# prototype.net
KiCad netlist of a schematic drawn in EAGLE
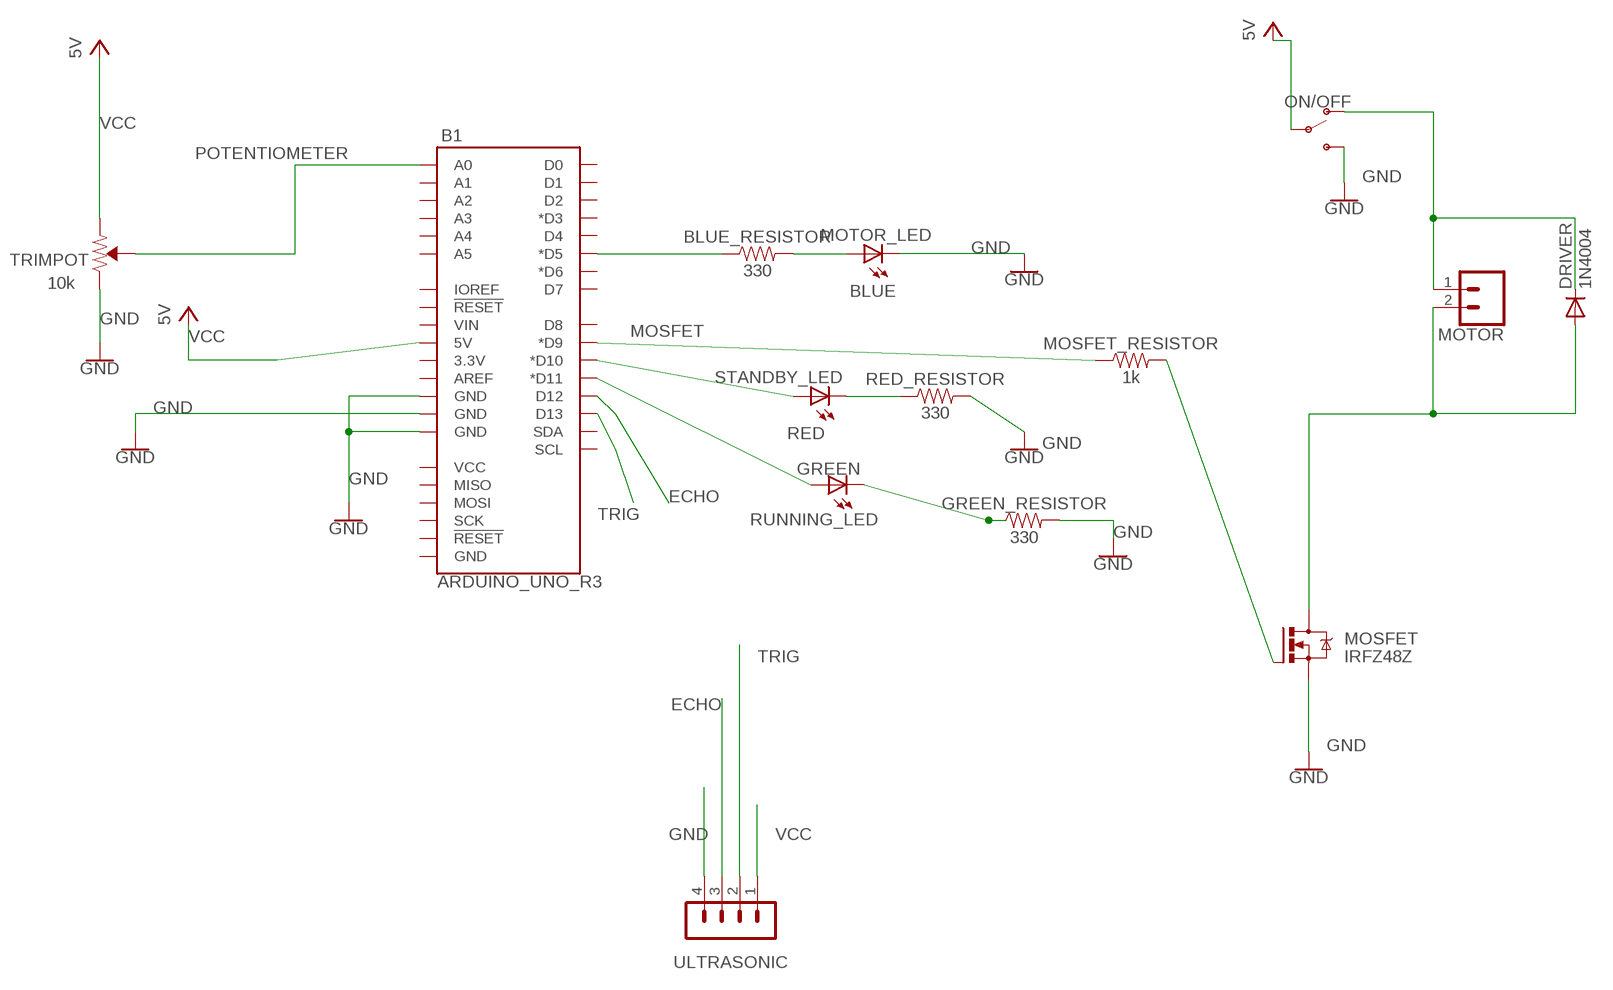
[diagram p0: schematic, sheet 1]

(export (version "E")
  (design (tool "Eeschema 10.0.6"))
  (components
    (comp (ref "B1")
      (value "ARDUINO_UNO_R3")
      (footprint "eagle-import:ARDUINO_R3")
      (libsource (lib "eagle-import") (part "ARDUINO_UNO_R3"))
    )
    (comp (ref "BLUE_RESISTOR")
      (value "330")
      (footprint "eagle-import:AXIAL-0.3")
      (libsource (lib "eagle-import") (part "1KOHM-HORIZ-1/4W-1%"))
    )
    (comp (ref "DRIVER")
      (value "1N4004")
      (footprint "eagle-import:DO41-10")
      (libsource (lib "eagle-import") (part "1N4004"))
    )
    (comp (ref "GREEN_RESISTOR")
      (value "330")
      (footprint "eagle-import:AXIAL-0.3")
      (libsource (lib "eagle-import") (part "330OHM-HORIZ-1/10W-5%"))
    )
    (comp (ref "MOSFET")
      (value "IRFZ48Z")
      (footprint "eagle-import:TO220BH")
      (libsource (lib "eagle-import") (part "IRFZ48Z"))
    )
    (comp (ref "MOSFET_RESISTOR")
      (value "1k")
      (footprint "eagle-import:AXIAL-0.3")
      (libsource (lib "eagle-import") (part "1KOHM-HORIZ-1/4W-1%"))
    )
    (comp (ref "MOTOR")
      (value "CONN_02")
      (footprint "eagle-import:1X02")
      (libsource (lib "eagle-import") (part "CONN_02"))
    )
    (comp (ref "MOTOR_LED")
      (value "BLUE")
      (footprint "eagle-import:LED5MM")
      (libsource (lib "eagle-import") (part "LED5MM"))
    )
    (comp (ref "ON/OFF")
      (value "SWITCH-SPDT-PTH-11.6X4.0MM")
      (footprint "eagle-import:SWITCH_SPDT_PTH_11.6X4.0MM")
      (libsource (lib "eagle-import") (part "SWITCH-SPDT-PTH-11.6X4.0MM"))
    )
    (comp (ref "RED_RESISTOR")
      (value "330")
      (footprint "eagle-import:AXIAL-0.3")
      (libsource (lib "eagle-import") (part "330OHM-HORIZ-1/10W-5%"))
    )
    (comp (ref "RUNNING_LED")
      (value "GREEN")
      (footprint "eagle-import:LED5MM")
      (libsource (lib "eagle-import") (part "LED5MM"))
    )
    (comp (ref "STANDBY_LED")
      (value "RED")
      (footprint "eagle-import:LED5MM")
      (libsource (lib "eagle-import") (part "LED5MM"))
    )
    (comp (ref "TRIMPOT")
      (value "10k")
      (footprint "eagle-import:TRIMPOT-PTH-3386U")
      (libsource (lib "eagle-import") (part "TRIMPOT-PTH-10MM-KNOB-1/2W-10%"))
    )
    (comp (ref "ULTRASONIC")
      (value "MA04-1")
      (footprint "eagle-import:MA04-1")
      (libsource (lib "eagle-import") (part "MA04-1"))
    )
  )
  (nets
    (net (code "1") (name "/ECHO") (class "Default")
      (node (ref "B1") (pin "D12") (pinfunction "D12_D12") (pintype "bidirectional"))
      (node (ref "ULTRASONIC") (pin "3") (pinfunction "3_3") (pintype "passive"))
    )
    (net (code "2") (name "/MOSFET") (class "Default")
      (node (ref "B1") (pin "D9") (pinfunction "*D9_D9") (pintype "bidirectional"))
      (node (ref "MOSFET_RESISTOR") (pin "P$1") (pinfunction "1_P$1") (pintype "passive"))
    )
    (net (code "3") (name "/POTENTIOMETER") (class "Default")
      (node (ref "B1") (pin "A0") (pinfunction "A0_A0") (pintype "bidirectional"))
      (node (ref "TRIMPOT") (pin "2") (pinfunction "WIPER_2") (pintype "passive"))
    )
    (net (code "4") (name "/TRIG") (class "Default")
      (node (ref "B1") (pin "D13") (pinfunction "D13_D13") (pintype "bidirectional"))
      (node (ref "ULTRASONIC") (pin "2") (pinfunction "2_2") (pintype "passive"))
    )
    (net (code "5") (name "5V") (class "Default")
      (node (ref "B1") (pin "5V") (pinfunction "5V_5V") (pintype "bidirectional"))
      (node (ref "ON/OFF") (pin "2") (pinfunction "P_2") (pintype "passive"))
      (node (ref "TRIMPOT") (pin "1") (pinfunction "CCW_1") (pintype "passive"))
      (node (ref "ULTRASONIC") (pin "1") (pinfunction "1_1") (pintype "passive"))
    )
    (net (code "6") (name "GND") (class "Default")
      (node (ref "B1") (pin "GND@2") (pinfunction "GND_GND@2") (pintype "bidirectional"))
      (node (ref "B1") (pin "GND@3") (pinfunction "GND_GND@3") (pintype "bidirectional"))
      (node (ref "B1") (pin "GND@4") (pinfunction "GND_GND@4") (pintype "bidirectional"))
      (node (ref "GREEN_RESISTOR") (pin "P$2") (pinfunction "2_P$2") (pintype "passive"))
      (node (ref "MOSFET") (pin "S") (pinfunction "S_S") (pintype "passive"))
      (node (ref "MOTOR_LED") (pin "K") (pinfunction "C_K") (pintype "passive"))
      (node (ref "ON/OFF") (pin "3") (pinfunction "S_3") (pintype "passive"))
      (node (ref "RED_RESISTOR") (pin "P$2") (pinfunction "2_P$2") (pintype "passive"))
      (node (ref "TRIMPOT") (pin "3") (pinfunction "CW_3") (pintype "passive"))
      (node (ref "ULTRASONIC") (pin "4") (pinfunction "4_4") (pintype "passive"))
    )
    (net (code "7") (name "Net-(B1-*D5)") (class "Default")
      (node (ref "B1") (pin "D5") (pinfunction "*D5_D5") (pintype "bidirectional"))
      (node (ref "BLUE_RESISTOR") (pin "P$1") (pinfunction "1_P$1") (pintype "passive"))
    )
    (net (code "8") (name "Net-(B1-*D10)") (class "Default")
      (node (ref "B1") (pin "D10") (pinfunction "*D10_D10") (pintype "bidirectional"))
      (node (ref "STANDBY_LED") (pin "A") (pinfunction "A_A") (pintype "passive"))
    )
    (net (code "9") (name "Net-(B1-*D11)") (class "Default")
      (node (ref "B1") (pin "D11") (pinfunction "*D11_D11") (pintype "bidirectional"))
      (node (ref "RUNNING_LED") (pin "A") (pinfunction "A_A") (pintype "passive"))
    )
    (net (code "10") (name "Net-(BLUE_RESISTOR-2)") (class "Default")
      (node (ref "BLUE_RESISTOR") (pin "P$2") (pinfunction "2_P$2") (pintype "passive"))
      (node (ref "MOTOR_LED") (pin "A") (pinfunction "A_A") (pintype "passive"))
    )
    (net (code "11") (name "Net-(DRIVER-PadA)") (class "Default")
      (node (ref "DRIVER") (pin "A") (pinfunction "A_A") (pintype "passive"))
      (node (ref "MOSFET") (pin "D") (pinfunction "D_D") (pintype "passive"))
      (node (ref "MOTOR") (pin "2") (pinfunction "2_2") (pintype "passive"))
    )
    (net (code "12") (name "Net-(GREEN_RESISTOR-1)") (class "Default")
      (node (ref "GREEN_RESISTOR") (pin "P$1") (pinfunction "1_P$1") (pintype "passive"))
      (node (ref "RUNNING_LED") (pin "K") (pinfunction "C_K") (pintype "passive"))
    )
    (net (code "13") (name "Net-(MOSFET_RESISTOR-2)") (class "Default")
      (node (ref "MOSFET") (pin "G") (pinfunction "G_G") (pintype "passive"))
      (node (ref "MOSFET_RESISTOR") (pin "P$2") (pinfunction "2_P$2") (pintype "passive"))
    )
    (net (code "14") (name "Net-(ON/OFF-O)") (class "Default")
      (node (ref "DRIVER") (pin "C") (pinfunction "C_C") (pintype "passive"))
      (node (ref "MOTOR") (pin "1") (pinfunction "1_1") (pintype "passive"))
      (node (ref "ON/OFF") (pin "1") (pinfunction "O_1") (pintype "passive"))
    )
    (net (code "15") (name "Net-(RED_RESISTOR-1)") (class "Default")
      (node (ref "RED_RESISTOR") (pin "P$1") (pinfunction "1_P$1") (pintype "passive"))
      (node (ref "STANDBY_LED") (pin "K") (pinfunction "C_K") (pintype "passive"))
    )
    (net (code "16") (name "unconnected-(B1-*D3-PadD3)") (class "Default")
      (node (ref "B1") (pin "D3") (pinfunction "*D3_D3") (pintype "bidirectional"))
    )
    (net (code "17") (name "unconnected-(B1-*D6-PadD6)") (class "Default")
      (node (ref "B1") (pin "D6") (pinfunction "*D6_D6") (pintype "bidirectional"))
    )
    (net (code "18") (name "unconnected-(B1-GND-PadGND@1)") (class "Default")
      (node (ref "B1") (pin "GND@1") (pinfunction "GND_GND@1") (pintype "bidirectional"))
    )
    (net (code "19") (name "unconnected-(B1-Pad3.3V)") (class "Default")
      (node (ref "B1") (pin "3.3V") (pinfunction "3.3V_3.3V") (pintype "bidirectional"))
    )
    (net (code "20") (name "unconnected-(B1-PadA1)") (class "Default")
      (node (ref "B1") (pin "A1") (pinfunction "A1_A1") (pintype "bidirectional"))
    )
    (net (code "21") (name "unconnected-(B1-PadA2)") (class "Default")
      (node (ref "B1") (pin "A2") (pinfunction "A2_A2") (pintype "bidirectional"))
    )
    (net (code "22") (name "unconnected-(B1-PadA3)") (class "Default")
      (node (ref "B1") (pin "A3") (pinfunction "A3_A3") (pintype "bidirectional"))
    )
    (net (code "23") (name "unconnected-(B1-PadA4)") (class "Default")
      (node (ref "B1") (pin "A4") (pinfunction "A4_A4") (pintype "bidirectional"))
    )
    (net (code "24") (name "unconnected-(B1-PadA5)") (class "Default")
      (node (ref "B1") (pin "A5") (pinfunction "A5_A5") (pintype "bidirectional"))
    )
    (net (code "25") (name "unconnected-(B1-PadAREF)") (class "Default")
      (node (ref "B1") (pin "AREF") (pinfunction "AREF_AREF") (pintype "bidirectional"))
    )
    (net (code "26") (name "unconnected-(B1-PadD0)") (class "Default")
      (node (ref "B1") (pin "D0") (pinfunction "D0_D0") (pintype "bidirectional"))
    )
    (net (code "27") (name "unconnected-(B1-PadD1)") (class "Default")
      (node (ref "B1") (pin "D1") (pinfunction "D1_D1") (pintype "bidirectional"))
    )
    (net (code "28") (name "unconnected-(B1-PadD2)") (class "Default")
      (node (ref "B1") (pin "D2") (pinfunction "D2_D2") (pintype "bidirectional"))
    )
    (net (code "29") (name "unconnected-(B1-PadD4)") (class "Default")
      (node (ref "B1") (pin "D4") (pinfunction "D4_D4") (pintype "bidirectional"))
    )
    (net (code "30") (name "unconnected-(B1-PadD7)") (class "Default")
      (node (ref "B1") (pin "D7") (pinfunction "D7_D7") (pintype "bidirectional"))
    )
    (net (code "31") (name "unconnected-(B1-PadD8)") (class "Default")
      (node (ref "B1") (pin "D8") (pinfunction "D8_D8") (pintype "bidirectional"))
    )
    (net (code "32") (name "unconnected-(B1-PadIOREF)") (class "Default")
      (node (ref "B1") (pin "IOREF") (pinfunction "IOREF_IOREF") (pintype "bidirectional"))
    )
    (net (code "33") (name "unconnected-(B1-PadMISO)") (class "Default")
      (node (ref "B1") (pin "MISO") (pinfunction "MISO_MISO") (pintype "bidirectional"))
    )
    (net (code "34") (name "unconnected-(B1-PadMOSI)") (class "Default")
      (node (ref "B1") (pin "MOSI") (pinfunction "MOSI_MOSI") (pintype "bidirectional"))
    )
    (net (code "35") (name "unconnected-(B1-PadSCK)") (class "Default")
      (node (ref "B1") (pin "SCK") (pinfunction "SCK_SCK") (pintype "bidirectional"))
    )
    (net (code "36") (name "unconnected-(B1-PadSCL)") (class "Default")
      (node (ref "B1") (pin "SCL") (pinfunction "SCL_SCL") (pintype "bidirectional"))
    )
    (net (code "37") (name "unconnected-(B1-PadSDA)") (class "Default")
      (node (ref "B1") (pin "SDA") (pinfunction "SDA_SDA") (pintype "bidirectional"))
    )
    (net (code "38") (name "unconnected-(B1-PadVCC)") (class "Default")
      (node (ref "B1") (pin "VCC") (pinfunction "VCC_VCC") (pintype "bidirectional"))
    )
    (net (code "39") (name "unconnected-(B1-PadVIN)") (class "Default")
      (node (ref "B1") (pin "VIN") (pinfunction "VIN_VIN") (pintype "bidirectional"))
    )
    (net (code "40") (name "unconnected-(B1-~{RESET}-PadRESET@1)") (class "Default")
      (node (ref "B1") (pin "RESET@1") (pinfunction "~{RESET}_RESET@1") (pintype "bidirectional"))
    )
    (net (code "41") (name "unconnected-(B1-~{RESET}-PadRESET@2)") (class "Default")
      (node (ref "B1") (pin "RESET@2") (pinfunction "~{RESET}_RESET@2") (pintype "bidirectional"))
    )
  )
)
